# msp430_minimal_schematic.net
KiCad netlist of a schematic drawn in EAGLE
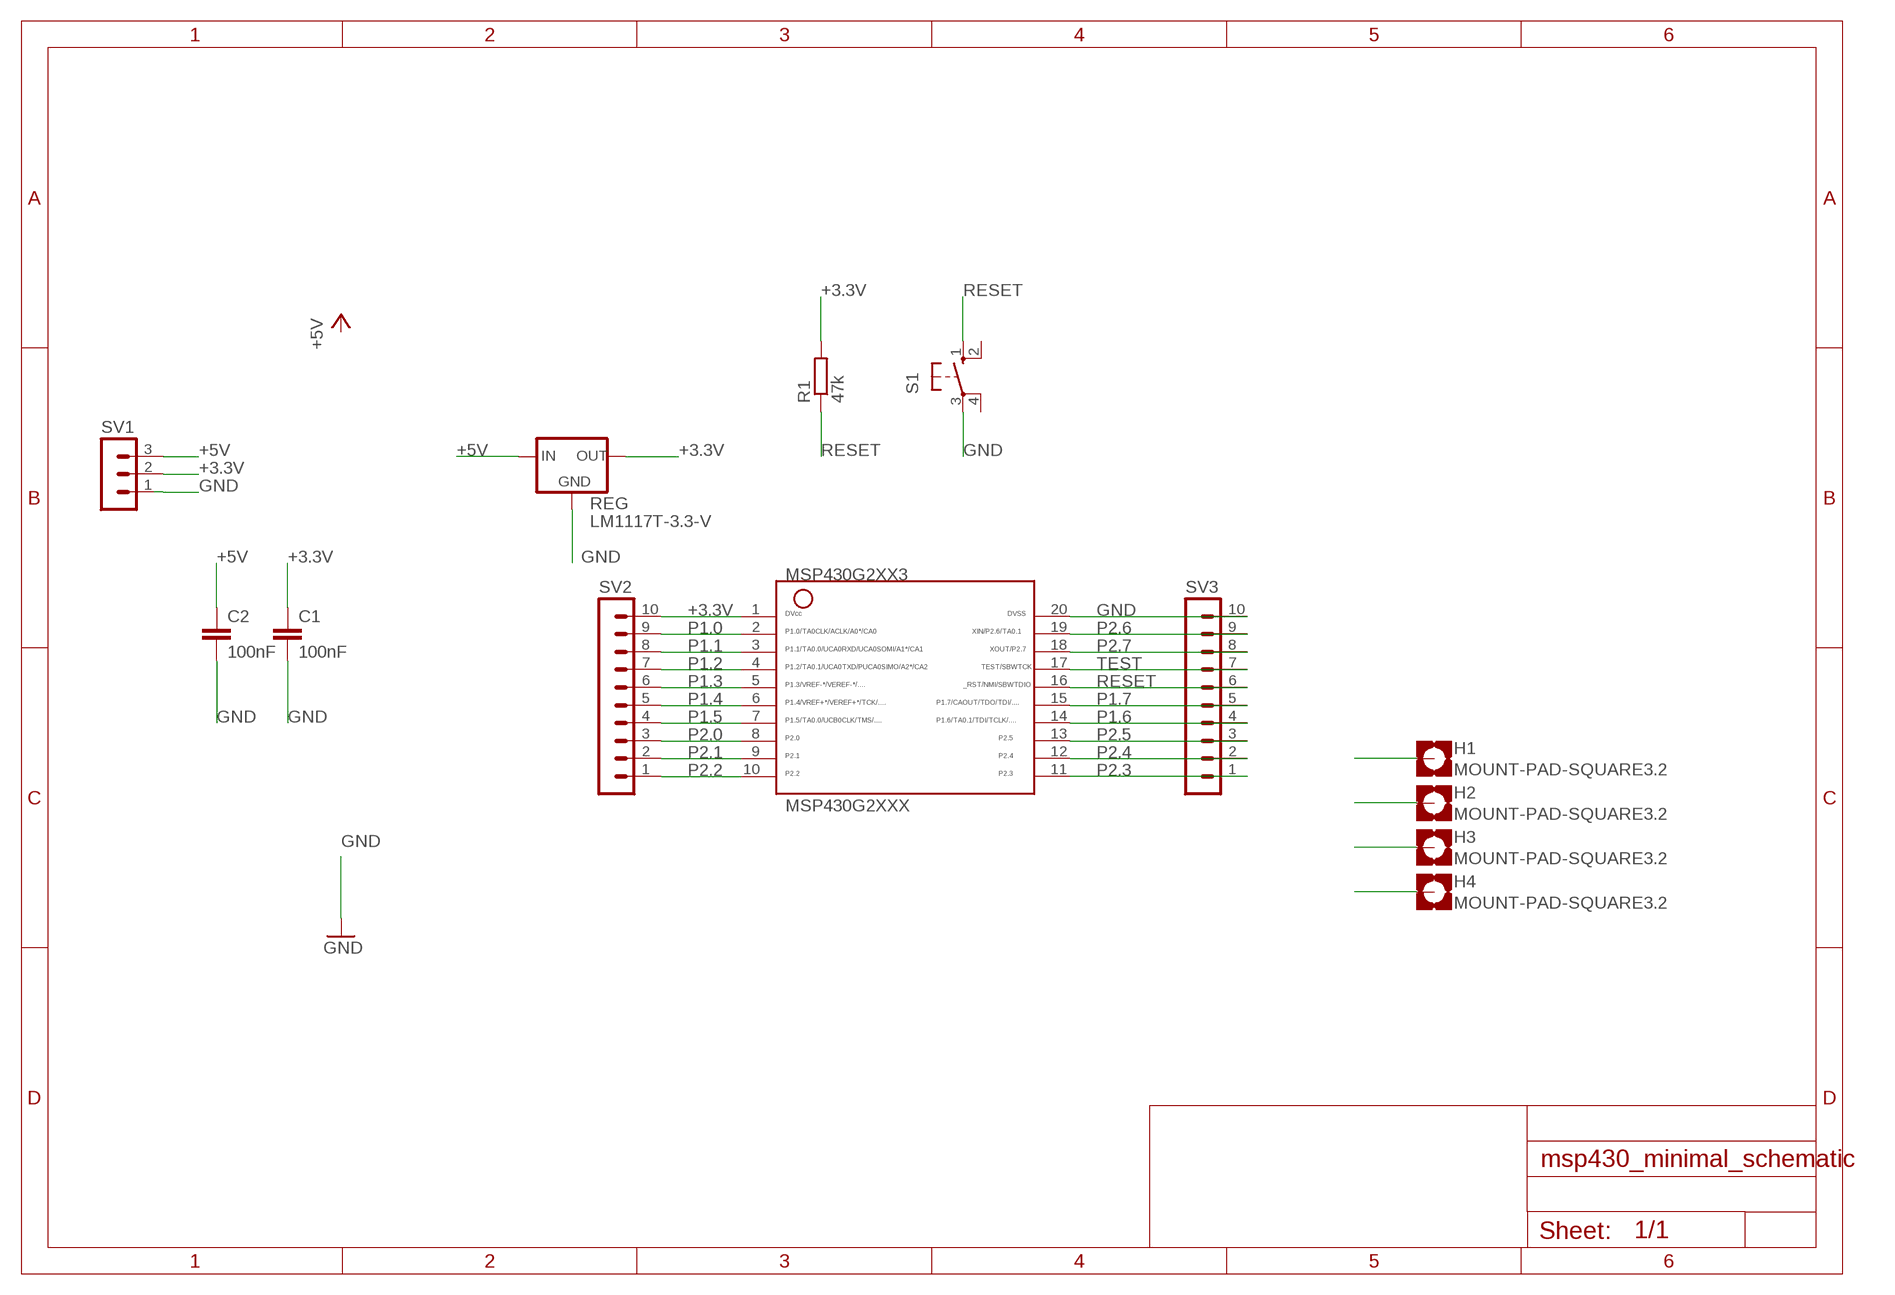
[diagram p0: schematic, sheet 1]

(export (version "E")
  (design (tool "Eeschema 10.0.6"))
  (components
    (comp (ref "C1")
      (value "100nF")
      (footprint "eagle-import:C050-030X075")
      (libsource (lib "eagle-import") (part "C-EU050-030X075"))
    )
    (comp (ref "C2")
      (value "100nF")
      (footprint "eagle-import:C050-030X075")
      (libsource (lib "eagle-import") (part "C-EU050-030X075"))
    )
    (comp (ref "H1")
      (value "MOUNT-PAD-SQUARE3.2")
      (footprint "eagle-import:3,2-PAD-SQUARE")
      (libsource (lib "eagle-import") (part "MOUNT-PAD-SQUARE3.2"))
    )
    (comp (ref "H2")
      (value "MOUNT-PAD-SQUARE3.2")
      (footprint "eagle-import:3,2-PAD-SQUARE")
      (libsource (lib "eagle-import") (part "MOUNT-PAD-SQUARE3.2"))
    )
    (comp (ref "H3")
      (value "MOUNT-PAD-SQUARE3.2")
      (footprint "eagle-import:3,2-PAD-SQUARE")
      (libsource (lib "eagle-import") (part "MOUNT-PAD-SQUARE3.2"))
    )
    (comp (ref "H4")
      (value "MOUNT-PAD-SQUARE3.2")
      (footprint "eagle-import:3,2-PAD-SQUARE")
      (libsource (lib "eagle-import") (part "MOUNT-PAD-SQUARE3.2"))
    )
    (comp (ref "MSP430G2XXX")
      (value "G2XX3---N20")
      (footprint "eagle-import:N20")
      (libsource (lib "eagle-import") (part "G2XX3---N20"))
    )
    (comp (ref "R1")
      (value "47k")
      (footprint "eagle-import:0204_7")
      (libsource (lib "eagle-import") (part "R-EU_0204/7"))
    )
    (comp (ref "REG")
      (value "LM1117T-3.3-V")
      (footprint "eagle-import:TO220V")
      (libsource (lib "eagle-import") (part "LM1117T--V3.3"))
    )
    (comp (ref "S1")
      (value "10-XX")
      (footprint "eagle-import:B3F-10XX")
      (fields (field (name "MPN") "B3F-1000"))
      (libsource (lib "eagle-import") (part "10-XX"))
    )
    (comp (ref "SV1")
      (value "MA03-1")
      (footprint "eagle-import:MA03-1")
      (libsource (lib "eagle-import") (part "MA03-1"))
    )
    (comp (ref "SV2")
      (value "MA10-1")
      (footprint "eagle-import:MA10-1")
      (libsource (lib "eagle-import") (part "MA10-1"))
    )
    (comp (ref "SV3")
      (value "MA10-1")
      (footprint "eagle-import:MA10-1")
      (libsource (lib "eagle-import") (part "MA10-1"))
    )
  )
  (nets
    (net (code "1") (name "+5V") (class "Default")
      (node (ref "C2") (pin "1") (pinfunction "1_1") (pintype "passive"))
      (node (ref "REG") (pin "3") (pinfunction "IN_3") (pintype "input"))
      (node (ref "SV1") (pin "3") (pinfunction "3_3") (pintype "passive"))
    )
    (net (code "2") (name "/+3.3V") (class "Default")
      (node (ref "C1") (pin "1") (pinfunction "1_1") (pintype "passive"))
      (node (ref "MSP430G2XXX") (pin "1") (pinfunction "1_1") (pintype "bidirectional"))
      (node (ref "R1") (pin "2") (pinfunction "2_2") (pintype "passive"))
      (node (ref "REG") (pin "2") (pinfunction "OUT_2") (pintype "passive"))
      (node (ref "SV1") (pin "2") (pinfunction "2_2") (pintype "passive"))
      (node (ref "SV2") (pin "10") (pinfunction "10_10") (pintype "passive"))
    )
    (net (code "3") (name "/P1.0") (class "Default")
      (node (ref "MSP430G2XXX") (pin "2") (pinfunction "2_2") (pintype "bidirectional"))
      (node (ref "SV2") (pin "9") (pinfunction "9_9") (pintype "passive"))
    )
    (net (code "4") (name "/P1.1") (class "Default")
      (node (ref "MSP430G2XXX") (pin "3") (pinfunction "3_3") (pintype "bidirectional"))
      (node (ref "SV2") (pin "8") (pinfunction "8_8") (pintype "passive"))
    )
    (net (code "5") (name "/P1.2") (class "Default")
      (node (ref "MSP430G2XXX") (pin "4") (pinfunction "4_4") (pintype "bidirectional"))
      (node (ref "SV2") (pin "7") (pinfunction "7_7") (pintype "passive"))
    )
    (net (code "6") (name "/P1.3") (class "Default")
      (node (ref "MSP430G2XXX") (pin "5") (pinfunction "5_5") (pintype "bidirectional"))
      (node (ref "SV2") (pin "6") (pinfunction "6_6") (pintype "passive"))
    )
    (net (code "7") (name "/P1.4") (class "Default")
      (node (ref "MSP430G2XXX") (pin "6") (pinfunction "6_6") (pintype "bidirectional"))
      (node (ref "SV2") (pin "5") (pinfunction "5_5") (pintype "passive"))
    )
    (net (code "8") (name "/P1.5") (class "Default")
      (node (ref "MSP430G2XXX") (pin "7") (pinfunction "7_7") (pintype "bidirectional"))
      (node (ref "SV2") (pin "4") (pinfunction "4_4") (pintype "passive"))
    )
    (net (code "9") (name "/P1.6") (class "Default")
      (node (ref "MSP430G2XXX") (pin "14") (pinfunction "14_14") (pintype "bidirectional"))
      (node (ref "SV3") (pin "4") (pinfunction "4_4") (pintype "passive"))
    )
    (net (code "10") (name "/P1.7") (class "Default")
      (node (ref "MSP430G2XXX") (pin "15") (pinfunction "15_15") (pintype "bidirectional"))
      (node (ref "SV3") (pin "5") (pinfunction "5_5") (pintype "passive"))
    )
    (net (code "11") (name "/P2.0") (class "Default")
      (node (ref "MSP430G2XXX") (pin "8") (pinfunction "8_8") (pintype "bidirectional"))
      (node (ref "SV2") (pin "3") (pinfunction "3_3") (pintype "passive"))
    )
    (net (code "12") (name "/P2.1") (class "Default")
      (node (ref "MSP430G2XXX") (pin "9") (pinfunction "9_9") (pintype "bidirectional"))
      (node (ref "SV2") (pin "2") (pinfunction "2_2") (pintype "passive"))
    )
    (net (code "13") (name "/P2.2") (class "Default")
      (node (ref "MSP430G2XXX") (pin "10") (pinfunction "10_10") (pintype "bidirectional"))
      (node (ref "SV2") (pin "1") (pinfunction "1_1") (pintype "passive"))
    )
    (net (code "14") (name "/P2.3") (class "Default")
      (node (ref "MSP430G2XXX") (pin "11") (pinfunction "11_11") (pintype "bidirectional"))
      (node (ref "SV3") (pin "1") (pinfunction "1_1") (pintype "passive"))
    )
    (net (code "15") (name "/P2.4") (class "Default")
      (node (ref "MSP430G2XXX") (pin "12") (pinfunction "12_12") (pintype "bidirectional"))
      (node (ref "SV3") (pin "2") (pinfunction "2_2") (pintype "passive"))
    )
    (net (code "16") (name "/P2.5") (class "Default")
      (node (ref "MSP430G2XXX") (pin "13") (pinfunction "13_13") (pintype "bidirectional"))
      (node (ref "SV3") (pin "3") (pinfunction "3_3") (pintype "passive"))
    )
    (net (code "17") (name "/P2.6") (class "Default")
      (node (ref "MSP430G2XXX") (pin "19") (pinfunction "19_19") (pintype "bidirectional"))
      (node (ref "SV3") (pin "9") (pinfunction "9_9") (pintype "passive"))
    )
    (net (code "18") (name "/P2.7") (class "Default")
      (node (ref "MSP430G2XXX") (pin "18") (pinfunction "18_18") (pintype "bidirectional"))
      (node (ref "SV3") (pin "8") (pinfunction "8_8") (pintype "passive"))
    )
    (net (code "19") (name "/RESET") (class "Default")
      (node (ref "MSP430G2XXX") (pin "16") (pinfunction "16_16") (pintype "bidirectional"))
      (node (ref "R1") (pin "1") (pinfunction "1_1") (pintype "passive"))
      (node (ref "S1") (pin "1") (pinfunction "S_1") (pintype "passive"))
      (node (ref "SV3") (pin "6") (pinfunction "6_6") (pintype "passive"))
    )
    (net (code "20") (name "/TEST") (class "Default")
      (node (ref "MSP430G2XXX") (pin "17") (pinfunction "17_17") (pintype "bidirectional"))
      (node (ref "SV3") (pin "7") (pinfunction "7_7") (pintype "passive"))
    )
    (net (code "21") (name "GND") (class "Default")
      (node (ref "C1") (pin "2") (pinfunction "2_2") (pintype "passive"))
      (node (ref "C2") (pin "2") (pinfunction "2_2") (pintype "passive"))
      (node (ref "H1") (pin "B3,2") (pinfunction "MOUNT_B3,2") (pintype "passive"))
      (node (ref "H2") (pin "B3,2") (pinfunction "MOUNT_B3,2") (pintype "passive"))
      (node (ref "H3") (pin "B3,2") (pinfunction "MOUNT_B3,2") (pintype "passive"))
      (node (ref "H4") (pin "B3,2") (pinfunction "MOUNT_B3,2") (pintype "passive"))
      (node (ref "MSP430G2XXX") (pin "20") (pinfunction "20_20") (pintype "bidirectional"))
      (node (ref "REG") (pin "1") (pinfunction "GND_1") (pintype "input"))
      (node (ref "S1") (pin "3") (pinfunction "P_3") (pintype "passive"))
      (node (ref "SV1") (pin "1") (pinfunction "1_1") (pintype "passive"))
      (node (ref "SV3") (pin "10") (pinfunction "10_10") (pintype "passive"))
    )
    (net (code "22") (name "unconnected-(S1-P1-Pad4)") (class "Default")
      (node (ref "S1") (pin "4") (pinfunction "P1_4") (pintype "passive"))
    )
    (net (code "23") (name "unconnected-(S1-S1-Pad2)") (class "Default")
      (node (ref "S1") (pin "2") (pinfunction "S1_2") (pintype "passive"))
    )
  )
)
